# Hockii-Control.net
KiCad netlist of a schematic drawn in EAGLE
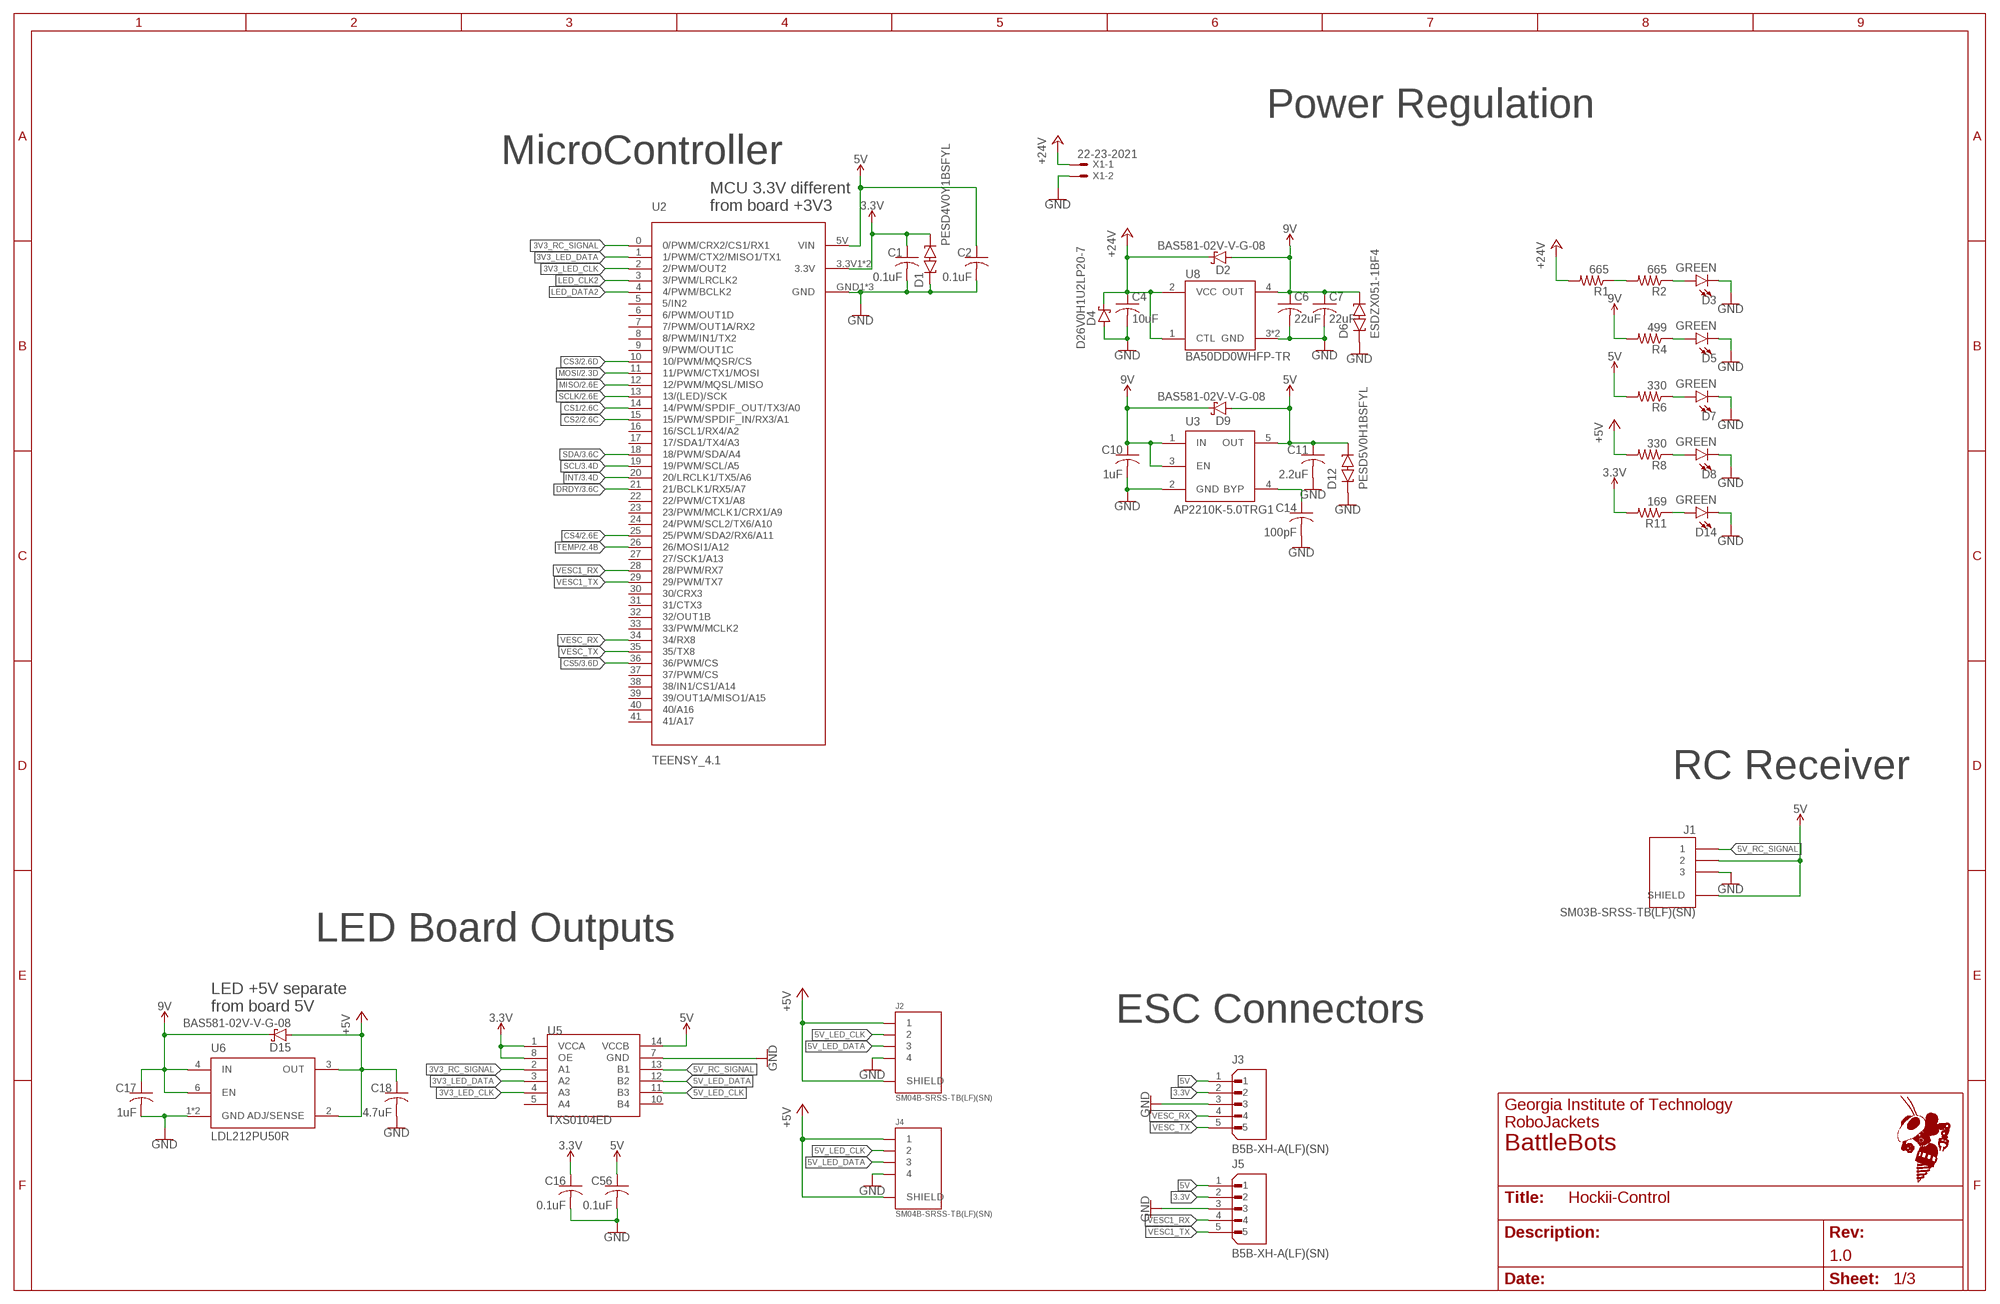
[diagram p0: schematic, sheet 1]
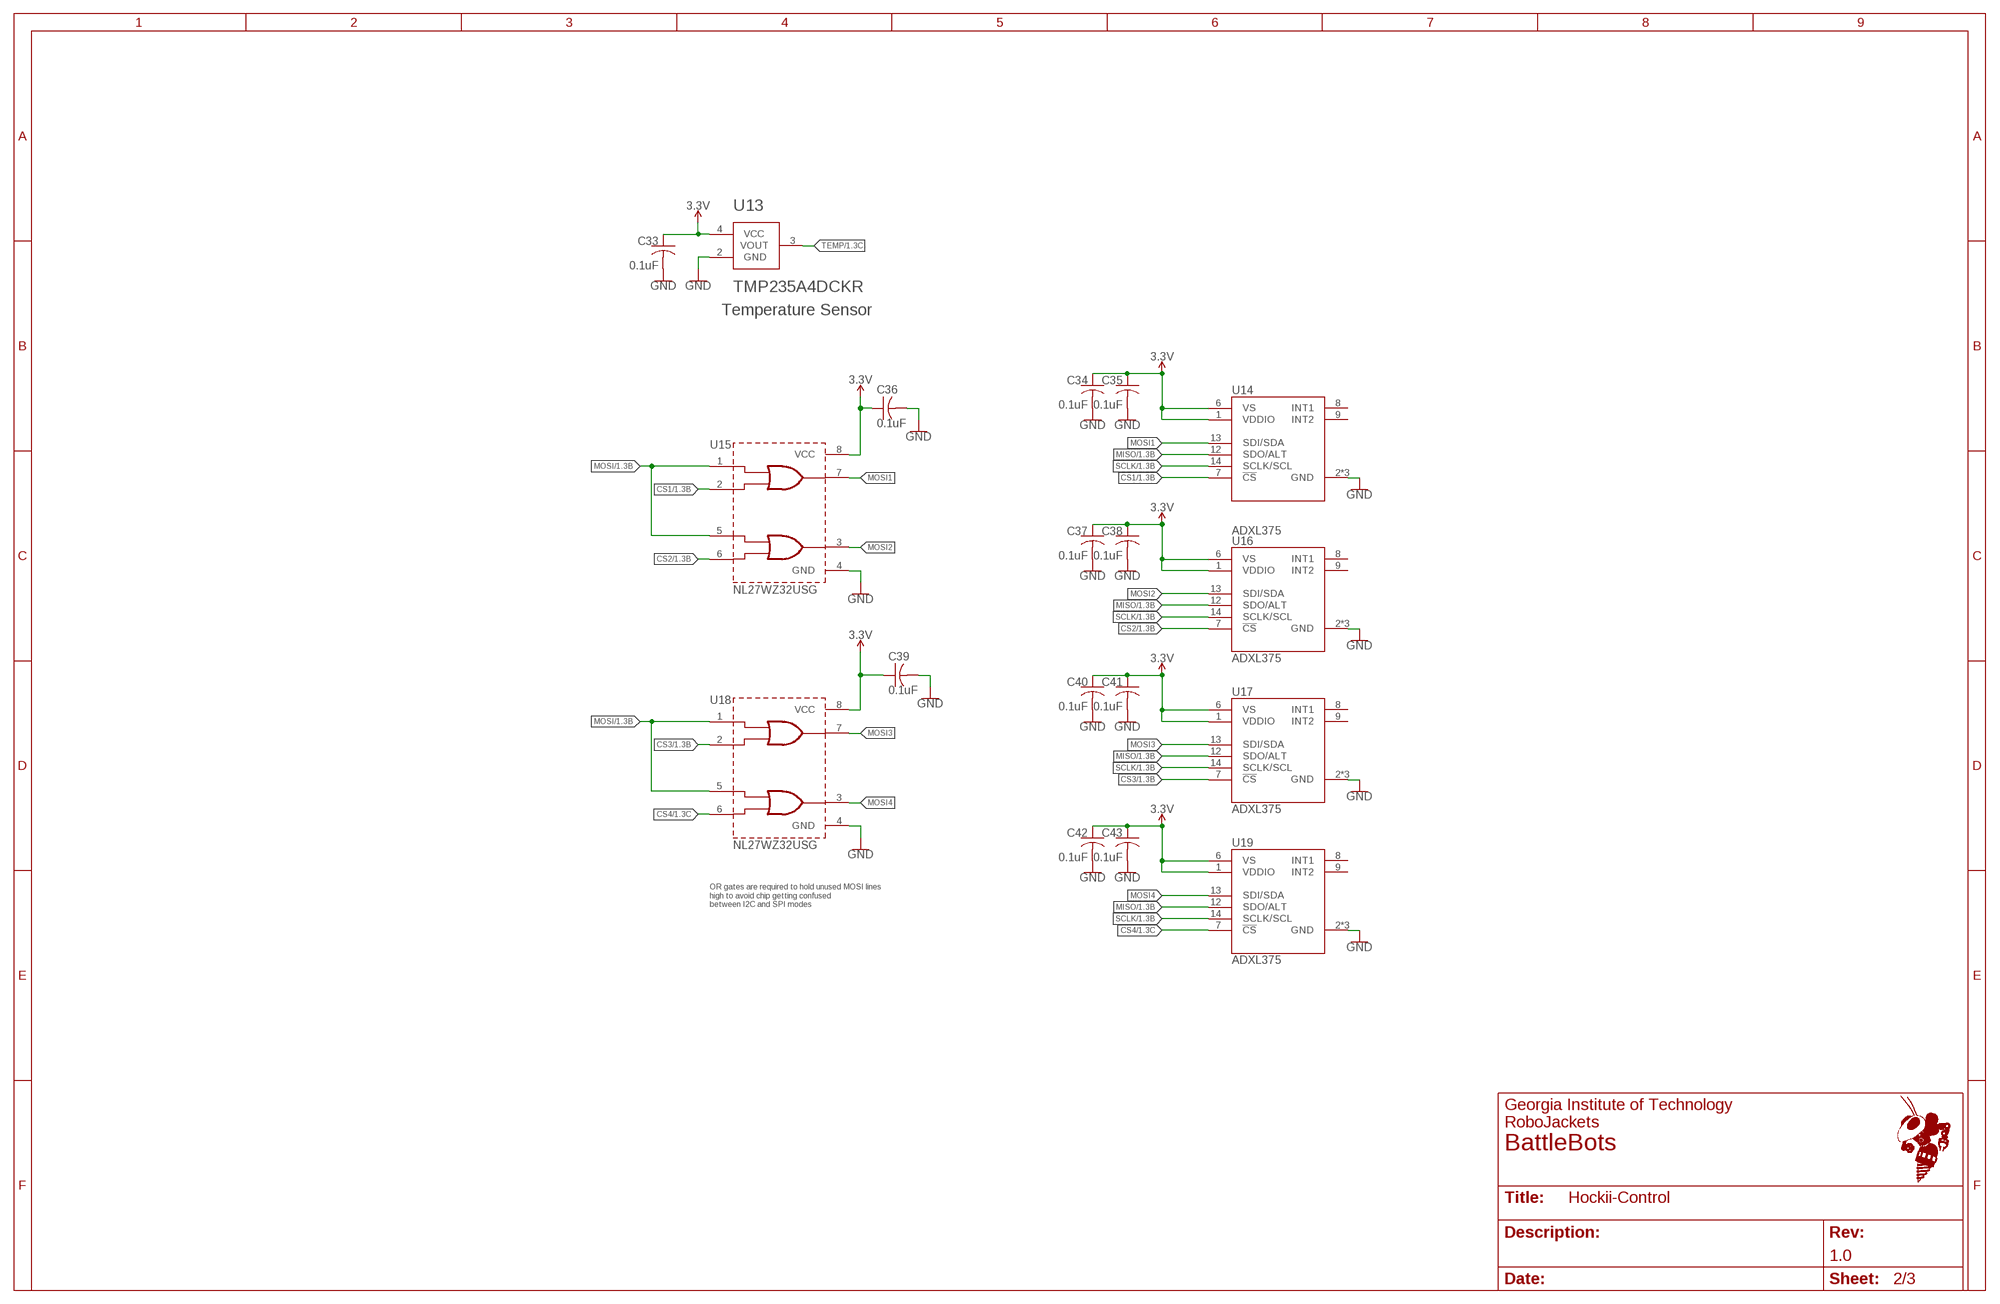
[diagram p1: schematic, sheet 2]
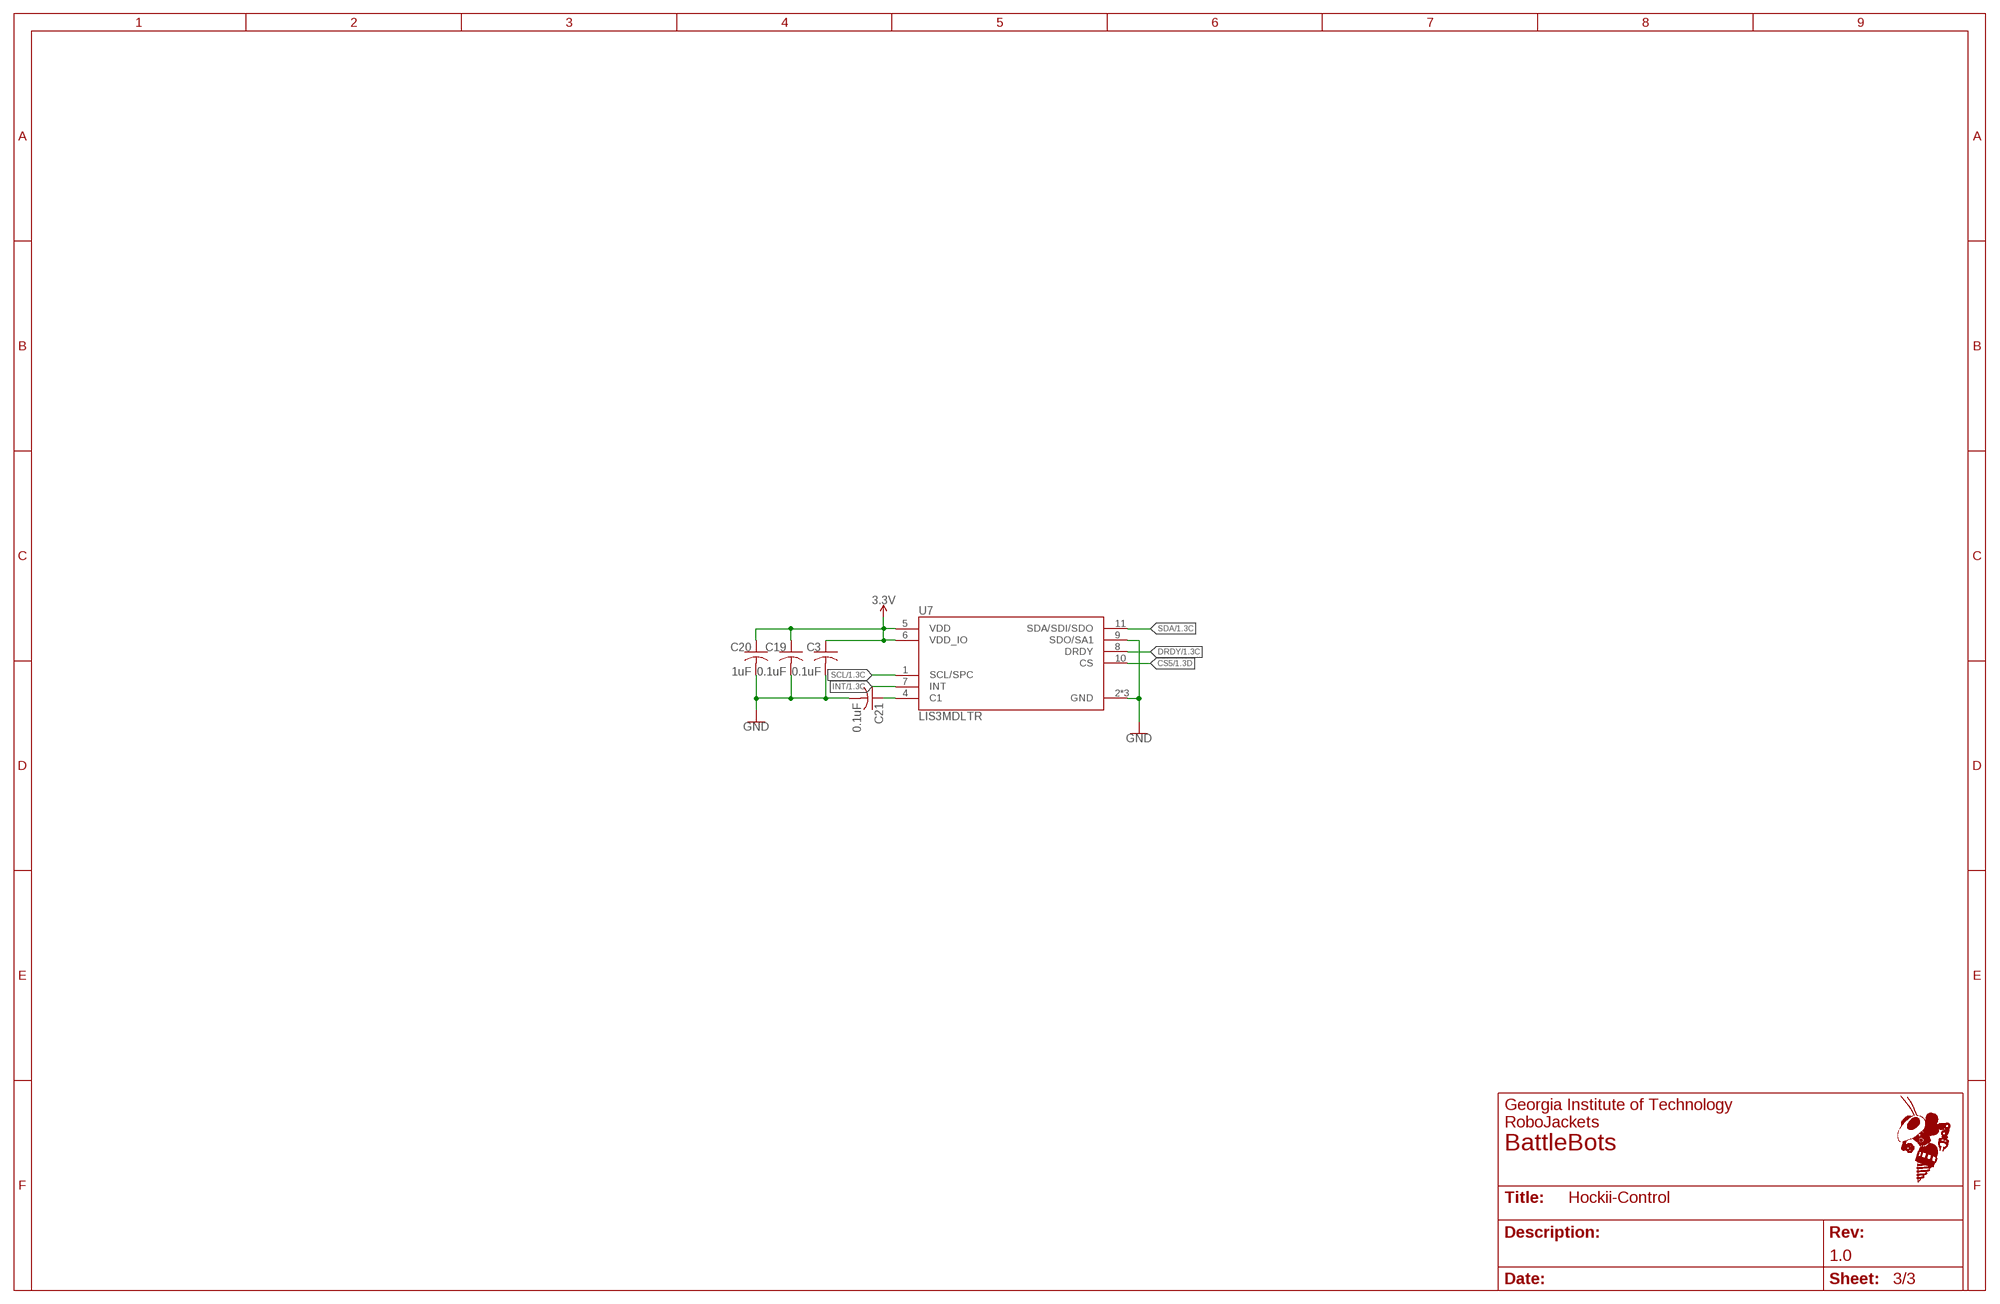
[diagram p2: schematic, sheet 3]

(export (version "E")
  (design (tool "Eeschema 10.0.6"))
  (components
    (comp (ref "C33")
      (value "0.1uF")
      (footprint "eagle-import:C0603")
      (libsource (lib "eagle-import") (part "C-USC0603"))
    )
    (comp (ref "C34")
      (value "0.1uF")
      (footprint "eagle-import:C0603")
      (libsource (lib "eagle-import") (part "C-USC0603"))
    )
    (comp (ref "C35")
      (value "0.1uF")
      (footprint "eagle-import:C0603")
      (libsource (lib "eagle-import") (part "C-USC0603"))
    )
    (comp (ref "C36")
      (value "0.1uF")
      (footprint "eagle-import:C0603")
      (libsource (lib "eagle-import") (part "C-USC0603"))
    )
    (comp (ref "C37")
      (value "0.1uF")
      (footprint "eagle-import:C0603")
      (libsource (lib "eagle-import") (part "C-USC0603"))
    )
    (comp (ref "C38")
      (value "0.1uF")
      (footprint "eagle-import:C0603")
      (libsource (lib "eagle-import") (part "C-USC0603"))
    )
    (comp (ref "C39")
      (value "0.1uF")
      (footprint "eagle-import:C0603")
      (libsource (lib "eagle-import") (part "C-USC0603"))
    )
    (comp (ref "C40")
      (value "0.1uF")
      (footprint "eagle-import:C0603")
      (libsource (lib "eagle-import") (part "C-USC0603"))
    )
    (comp (ref "C41")
      (value "0.1uF")
      (footprint "eagle-import:C0603")
      (libsource (lib "eagle-import") (part "C-USC0603"))
    )
    (comp (ref "C42")
      (value "0.1uF")
      (footprint "eagle-import:C0603")
      (libsource (lib "eagle-import") (part "C-USC0603"))
    )
    (comp (ref "C43")
      (value "0.1uF")
      (footprint "eagle-import:C0603")
      (libsource (lib "eagle-import") (part "C-USC0603"))
    )
    (comp (ref "U13")
      (value "TMP235A4DCKR")
      (footprint "eagle-import:SOT-353")
      (libsource (lib "eagle-import") (part "TMP235A4DCKR"))
    )
    (comp (ref "U14")
      (value "ADXL375")
      (footprint "eagle-import:14-LGA")
      (libsource (lib "eagle-import") (part "ADXL375"))
    )
    (comp (ref "U15")
      (value "NL27WZ32USG")
      (footprint "eagle-import:US8")
      (libsource (lib "eagle-import") (part "NL27WZ32USG"))
    )
    (comp (ref "U16")
      (value "ADXL375")
      (footprint "eagle-import:14-LGA")
      (libsource (lib "eagle-import") (part "ADXL375"))
    )
    (comp (ref "U17")
      (value "ADXL375")
      (footprint "eagle-import:14-LGA")
      (libsource (lib "eagle-import") (part "ADXL375"))
    )
    (comp (ref "U18")
      (value "NL27WZ32USG")
      (footprint "eagle-import:US8")
      (libsource (lib "eagle-import") (part "NL27WZ32USG"))
    )
    (comp (ref "U19")
      (value "ADXL375")
      (footprint "eagle-import:14-LGA")
      (libsource (lib "eagle-import") (part "ADXL375"))
    )
    (comp (ref "C3")
      (value "0.1uF")
      (footprint "eagle-import:C0603")
      (libsource (lib "eagle-import") (part "C-USC0603"))
    )
    (comp (ref "C19")
      (value "0.1uF")
      (footprint "eagle-import:C0603")
      (libsource (lib "eagle-import") (part "C-USC0603"))
    )
    (comp (ref "C20")
      (value "1uF")
      (footprint "eagle-import:C0603")
      (libsource (lib "eagle-import") (part "C-USC0603"))
    )
    (comp (ref "C21")
      (value "0.1uF")
      (footprint "eagle-import:C0603")
      (libsource (lib "eagle-import") (part "C-USC0603"))
    )
    (comp (ref "U7")
      (value "LIS3MDLTR")
      (footprint "eagle-import:LGA-12_2X2X1_STM")
      (libsource (lib "eagle-import") (part "LIS3MDLTR"))
    )
    (comp (ref "C1")
      (value "0.1uF")
      (footprint "eagle-import:C0603")
      (libsource (lib "eagle-import") (part "C-USC0603"))
    )
    (comp (ref "C2")
      (value "0.1uF")
      (footprint "eagle-import:C0603")
      (libsource (lib "eagle-import") (part "C-USC0603"))
    )
    (comp (ref "C4")
      (value "10uF")
      (footprint "eagle-import:C1206")
      (libsource (lib "eagle-import") (part "C-USC1206"))
    )
    (comp (ref "C6")
      (value "22uF")
      (footprint "eagle-import:C1206")
      (libsource (lib "eagle-import") (part "C-USC1206"))
    )
    (comp (ref "C7")
      (value "22uF")
      (footprint "eagle-import:C1206")
      (libsource (lib "eagle-import") (part "C-USC1206"))
    )
    (comp (ref "C10")
      (value "1uF")
      (footprint "eagle-import:C0603")
      (libsource (lib "eagle-import") (part "C-USC0603"))
    )
    (comp (ref "C11")
      (value "2.2uF")
      (footprint "eagle-import:C0603")
      (libsource (lib "eagle-import") (part "C-USC0603"))
    )
    (comp (ref "C14")
      (value "100pF")
      (footprint "eagle-import:C0603")
      (libsource (lib "eagle-import") (part "C-USC0603"))
    )
    (comp (ref "C16")
      (value "0.1uF")
      (footprint "eagle-import:C0603")
      (libsource (lib "eagle-import") (part "C-USC0603"))
    )
    (comp (ref "C17")
      (value "1uF")
      (footprint "eagle-import:C0603")
      (libsource (lib "eagle-import") (part "C-USC0603"))
    )
    (comp (ref "C18")
      (value "4.7uF")
      (footprint "eagle-import:C0603")
      (libsource (lib "eagle-import") (part "C-USC0603"))
    )
    (comp (ref "C56")
      (value "0.1uF")
      (footprint "eagle-import:C0603")
      (libsource (lib "eagle-import") (part "C-USC0603"))
    )
    (comp (ref "D1")
      (value "PESD4V0Y1BSFYL")
      (footprint "eagle-import:DSN0603-2")
      (libsource (lib "eagle-import") (part "PESD4V0Y1BSFYL"))
    )
    (comp (ref "D2")
      (value "BAS581-02V-V-G-08")
      (footprint "eagle-import:SOD-523")
      (libsource (lib "eagle-import") (part "BAS581-02V-V-G-08"))
    )
    (comp (ref "D3")
      (value "GREEN")
      (footprint "eagle-import:LED-0603")
      (libsource (lib "eagle-import") (part "LED-GREEN0603"))
    )
    (comp (ref "D4")
      (value "D26V0H1U2LP20-7")
      (footprint "eagle-import:D26V0H1U2LP20-7")
      (libsource (lib "eagle-import") (part "D26V0H1U2LP20-7"))
    )
    (comp (ref "D5")
      (value "GREEN")
      (footprint "eagle-import:LED-0603")
      (libsource (lib "eagle-import") (part "LED-GREEN0603"))
    )
    (comp (ref "D6")
      (value "ESDZX051-1BF4")
      (footprint "eagle-import:DSN0603-2")
      (libsource (lib "eagle-import") (part "ESDZX051-1BF4"))
    )
    (comp (ref "D7")
      (value "GREEN")
      (footprint "eagle-import:LED-0603")
      (libsource (lib "eagle-import") (part "LED-GREEN0603"))
    )
    (comp (ref "D8")
      (value "GREEN")
      (footprint "eagle-import:LED-0603")
      (libsource (lib "eagle-import") (part "LED-GREEN0603"))
    )
    (comp (ref "D9")
      (value "BAS581-02V-V-G-08")
      (footprint "eagle-import:SOD-523")
      (libsource (lib "eagle-import") (part "BAS581-02V-V-G-08"))
    )
    (comp (ref "D12")
      (value "PESD5V0H1BSFYL")
      (footprint "eagle-import:DSN0603-2")
      (libsource (lib "eagle-import") (part "PESD5V0H1BSFYL"))
    )
    (comp (ref "D14")
      (value "GREEN")
      (footprint "eagle-import:LED-0603")
      (libsource (lib "eagle-import") (part "LED-GREEN0603"))
    )
    (comp (ref "D15")
      (value "BAS581-02V-V-G-08")
      (footprint "eagle-import:SOD-523")
      (libsource (lib "eagle-import") (part "BAS581-02V-V-G-08"))
    )
    (comp (ref "J1")
      (value "SM03B-SRSS-TB(LF)(SN)")
      (footprint "eagle-import:SM03B-SRSS-TB(LF)(SN)")
      (libsource (lib "eagle-import") (part "SM03B-SRSS-TB(LF)(SN)"))
    )
    (comp (ref "J2")
      (value "SM04B-SRSS-TB(LF)(SN)")
      (footprint "eagle-import:SM04B-SRSS-TB(LF)(SN)")
      (libsource (lib "eagle-import") (part "SM04B-SRSS-TB(LF)(SN)"))
    )
    (comp (ref "J3")
      (value "B5B-XH-A(LF)(SN)")
      (footprint "eagle-import:JST_B5B-XH-A(LF)(SN)")
      (fields (field (name "MF") "JST Sales America Inc."))
      (libsource (lib "eagle-import") (part "B5B-XH-A(LF)(SN)"))
    )
    (comp (ref "J4")
      (value "SM04B-SRSS-TB(LF)(SN)")
      (footprint "eagle-import:SM04B-SRSS-TB(LF)(SN)")
      (libsource (lib "eagle-import") (part "SM04B-SRSS-TB(LF)(SN)"))
    )
    (comp (ref "J5")
      (value "B5B-XH-A(LF)(SN)")
      (footprint "eagle-import:JST_B5B-XH-A(LF)(SN)")
      (fields (field (name "MF") "JST Sales America Inc."))
      (libsource (lib "eagle-import") (part "B5B-XH-A(LF)(SN)"))
    )
    (comp (ref "R1")
      (value "665")
      (footprint "eagle-import:R0603")
      (libsource (lib "eagle-import") (part "R-US_R0603"))
    )
    (comp (ref "R2")
      (value "665")
      (footprint "eagle-import:R0603")
      (libsource (lib "eagle-import") (part "R-US_R0603"))
    )
    (comp (ref "R4")
      (value "499")
      (footprint "eagle-import:R0603")
      (libsource (lib "eagle-import") (part "R-US_R0603"))
    )
    (comp (ref "R6")
      (value "330")
      (footprint "eagle-import:R0603")
      (libsource (lib "eagle-import") (part "R-US_R0603"))
    )
    (comp (ref "R8")
      (value "330")
      (footprint "eagle-import:R0603")
      (libsource (lib "eagle-import") (part "R-US_R0603"))
    )
    (comp (ref "R11")
      (value "169")
      (footprint "eagle-import:R0603")
      (libsource (lib "eagle-import") (part "R-US_R0603"))
    )
    (comp (ref "U2")
      (value "TEENSY_4.1")
      (footprint "eagle-import:TEENSY_4.1")
      (libsource (lib "eagle-import") (part "TEENSY_4.1"))
    )
    (comp (ref "U3")
      (value "AP2210K-5.0TRG1")
      (footprint "eagle-import:SOT-23-5")
      (libsource (lib "eagle-import") (part "AP2210K-TRG15.0"))
    )
    (comp (ref "U5")
      (value "TXS0104ED")
      (footprint "eagle-import:14-SOIC")
      (libsource (lib "eagle-import") (part "TXS0104ED"))
    )
    (comp (ref "U6")
      (value "LDL212PU50R")
      (footprint "eagle-import:DFN6(3X3)")
      (libsource (lib "eagle-import") (part "LDL212PU50R"))
    )
    (comp (ref "U8")
      (value "BA50DD0WHFP-TR")
      (footprint "eagle-import:HRP5")
      (libsource (lib "eagle-import") (part "BA50DD0WHFP-TR"))
    )
    (comp (ref "X1")
      (value "22-23-2021")
      (footprint "eagle-import:22-23-2021")
      (fields (field (name "MF") "MOLEX"))
      (libsource (lib "eagle-import") (part "22-23-2021"))
    )
  )
  (nets
    (net (code "1") (name "+5V") (class "Default")
      (node (ref "C18") (pin "1") (pinfunction "1_1") (pintype "passive"))
      (node (ref "D15") (pin "2") (pinfunction "A_2") (pintype "passive"))
      (node (ref "J2") (pin "1") (pinfunction "1_1") (pintype "passive"))
      (node (ref "J2") (pin "S1") (pinfunction "SHIELD_S1") (pintype "passive"))
      (node (ref "J2") (pin "S2") (pinfunction "SHIELD_S2") (pintype "passive"))
      (node (ref "J4") (pin "1") (pinfunction "1_1") (pintype "passive"))
      (node (ref "J4") (pin "S1") (pinfunction "SHIELD_S1") (pintype "passive"))
      (node (ref "J4") (pin "S2") (pinfunction "SHIELD_S2") (pintype "passive"))
      (node (ref "R8") (pin "2") (pinfunction "2_2") (pintype "passive"))
      (node (ref "U6") (pin "2") (pinfunction "ADJ/SENSE_2") (pintype "bidirectional"))
      (node (ref "U6") (pin "3") (pinfunction "OUT_3") (pintype "passive"))
    )
    (net (code "2") (name "+24V") (class "Default")
      (node (ref "C4") (pin "1") (pinfunction "1_1") (pintype "passive"))
      (node (ref "D2") (pin "1") (pinfunction "C_1") (pintype "passive"))
      (node (ref "D4") (pin "1") (pinfunction "C_1") (pintype "passive"))
      (node (ref "R1") (pin "2") (pinfunction "2_2") (pintype "passive"))
      (node (ref "U8") (pin "1") (pinfunction "CTL_1") (pintype "input"))
      (node (ref "U8") (pin "2") (pinfunction "VCC_2") (pintype "power_in"))
      (node (ref "X1") (pin "1") (pinfunction "S_1") (pintype "passive"))
    )
    (net (code "3") (name "3.3V") (class "Default")
      (node (ref "C1") (pin "1") (pinfunction "1_1") (pintype "passive"))
      (node (ref "C16") (pin "1") (pinfunction "1_1") (pintype "passive"))
      (node (ref "C19") (pin "1") (pinfunction "1_1") (pintype "passive"))
      (node (ref "C20") (pin "1") (pinfunction "1_1") (pintype "passive"))
      (node (ref "C3") (pin "1") (pinfunction "1_1") (pintype "passive"))
      (node (ref "C33") (pin "1") (pinfunction "1_1") (pintype "passive"))
      (node (ref "C34") (pin "1") (pinfunction "1_1") (pintype "passive"))
      (node (ref "C35") (pin "1") (pinfunction "1_1") (pintype "passive"))
      (node (ref "C36") (pin "1") (pinfunction "1_1") (pintype "passive"))
      (node (ref "C37") (pin "1") (pinfunction "1_1") (pintype "passive"))
      (node (ref "C38") (pin "1") (pinfunction "1_1") (pintype "passive"))
      (node (ref "C39") (pin "1") (pinfunction "1_1") (pintype "passive"))
      (node (ref "C40") (pin "1") (pinfunction "1_1") (pintype "passive"))
      (node (ref "C41") (pin "1") (pinfunction "1_1") (pintype "passive"))
      (node (ref "C42") (pin "1") (pinfunction "1_1") (pintype "passive"))
      (node (ref "C43") (pin "1") (pinfunction "1_1") (pintype "passive"))
      (node (ref "D1") (pin "C2") (pinfunction "C2_C2") (pintype "passive"))
      (node (ref "J3") (pin "2") (pinfunction "2_2") (pintype "passive"))
      (node (ref "J5") (pin "2") (pinfunction "2_2") (pintype "passive"))
      (node (ref "R11") (pin "2") (pinfunction "2_2") (pintype "passive"))
      (node (ref "U13") (pin "4") (pinfunction "VCC_4") (pintype "passive"))
      (node (ref "U14") (pin "1") (pinfunction "VDDIO_1") (pintype "passive"))
      (node (ref "U14") (pin "6") (pinfunction "VS_6") (pintype "passive"))
      (node (ref "U15") (pin "8") (pinfunction "VCC_8") (pintype "passive"))
      (node (ref "U16") (pin "1") (pinfunction "VDDIO_1") (pintype "passive"))
      (node (ref "U16") (pin "6") (pinfunction "VS_6") (pintype "passive"))
      (node (ref "U17") (pin "1") (pinfunction "VDDIO_1") (pintype "passive"))
      (node (ref "U17") (pin "6") (pinfunction "VS_6") (pintype "passive"))
      (node (ref "U18") (pin "8") (pinfunction "VCC_8") (pintype "passive"))
      (node (ref "U19") (pin "1") (pinfunction "VDDIO_1") (pintype "passive"))
      (node (ref "U19") (pin "6") (pinfunction "VS_6") (pintype "passive"))
      (node (ref "U2") (pin "3.3V1") (pinfunction "3.3V_3.3V1") (pintype "passive"))
      (node (ref "U2") (pin "3.3V2") (pinfunction "3.3V_3.3V2") (pintype "passive"))
      (node (ref "U5") (pin "1") (pinfunction "VCCA_1") (pintype "passive"))
      (node (ref "U5") (pin "8") (pinfunction "OE_8") (pintype "passive"))
      (node (ref "U7") (pin "5") (pinfunction "VDD_5") (pintype "passive"))
      (node (ref "U7") (pin "6") (pinfunction "VDD_IO_6") (pintype "passive"))
    )
    (net (code "4") (name "3V3_LED_CLK") (class "Default")
      (node (ref "U2") (pin "2") (pinfunction "2/PWM/OUT2_2") (pintype "passive"))
      (node (ref "U5") (pin "4") (pinfunction "A3_4") (pintype "passive"))
    )
    (net (code "5") (name "3V3_LED_DATA") (class "Default")
      (node (ref "U2") (pin "1") (pinfunction "1/PWM/CTX2/MISO1/TX1_1") (pintype "passive"))
      (node (ref "U5") (pin "3") (pinfunction "A2_3") (pintype "passive"))
    )
    (net (code "6") (name "3V3_RC_SIGNAL") (class "Default")
      (node (ref "U2") (pin "0") (pinfunction "0/PWM/CRX2/CS1/RX1_0") (pintype "passive"))
      (node (ref "U5") (pin "2") (pinfunction "A1_2") (pintype "passive"))
    )
    (net (code "7") (name "5V") (class "Default")
      (node (ref "C11") (pin "1") (pinfunction "1_1") (pintype "passive"))
      (node (ref "C2") (pin "1") (pinfunction "1_1") (pintype "passive"))
      (node (ref "C56") (pin "1") (pinfunction "1_1") (pintype "passive"))
      (node (ref "D12") (pin "C2") (pinfunction "C2_C2") (pintype "passive"))
      (node (ref "D9") (pin "2") (pinfunction "A_2") (pintype "passive"))
      (node (ref "J1") (pin "2") (pinfunction "2_2") (pintype "passive"))
      (node (ref "J1") (pin "S1") (pinfunction "SHIELD_S1") (pintype "passive"))
      (node (ref "J1") (pin "S2") (pinfunction "SHIELD_S2") (pintype "passive"))
      (node (ref "J3") (pin "1") (pinfunction "1_1") (pintype "passive"))
      (node (ref "J5") (pin "1") (pinfunction "1_1") (pintype "passive"))
      (node (ref "R6") (pin "2") (pinfunction "2_2") (pintype "passive"))
      (node (ref "U2") (pin "5V") (pinfunction "VIN_5V") (pintype "passive"))
      (node (ref "U3") (pin "5") (pinfunction "OUT_5") (pintype "passive"))
      (node (ref "U5") (pin "14") (pinfunction "VCCB_14") (pintype "passive"))
    )
    (net (code "8") (name "5V_LED_CLK") (class "Default")
      (node (ref "J2") (pin "2") (pinfunction "2_2") (pintype "passive"))
      (node (ref "J4") (pin "2") (pinfunction "2_2") (pintype "passive"))
      (node (ref "U5") (pin "11") (pinfunction "B3_11") (pintype "passive"))
    )
    (net (code "9") (name "5V_LED_DATA") (class "Default")
      (node (ref "J2") (pin "3") (pinfunction "3_3") (pintype "passive"))
      (node (ref "J4") (pin "3") (pinfunction "3_3") (pintype "passive"))
      (node (ref "U5") (pin "12") (pinfunction "B2_12") (pintype "passive"))
    )
    (net (code "10") (name "5V_RC_SIGNAL") (class "Default")
      (node (ref "J1") (pin "1") (pinfunction "1_1") (pintype "passive"))
      (node (ref "U5") (pin "13") (pinfunction "B1_13") (pintype "passive"))
    )
    (net (code "11") (name "9V") (class "Default")
      (node (ref "C10") (pin "1") (pinfunction "1_1") (pintype "passive"))
      (node (ref "C17") (pin "1") (pinfunction "1_1") (pintype "passive"))
      (node (ref "C6") (pin "1") (pinfunction "1_1") (pintype "passive"))
      (node (ref "C7") (pin "1") (pinfunction "1_1") (pintype "passive"))
      (node (ref "D15") (pin "1") (pinfunction "C_1") (pintype "passive"))
      (node (ref "D2") (pin "2") (pinfunction "A_2") (pintype "passive"))
      (node (ref "D6") (pin "C2") (pinfunction "C2_C2") (pintype "passive"))
      (node (ref "D9") (pin "1") (pinfunction "C_1") (pintype "passive"))
      (node (ref "R4") (pin "2") (pinfunction "2_2") (pintype "passive"))
      (node (ref "U3") (pin "1") (pinfunction "IN_1") (pintype "passive"))
      (node (ref "U3") (pin "3") (pinfunction "EN_3") (pintype "passive"))
      (node (ref "U6") (pin "4") (pinfunction "IN_4") (pintype "passive"))
      (node (ref "U6") (pin "6") (pinfunction "EN_6") (pintype "passive"))
      (node (ref "U8") (pin "4") (pinfunction "OUT_4") (pintype "output"))
    )
    (net (code "12") (name "CS1") (class "Default")
      (node (ref "U14") (pin "7") (pinfunction "~{CS}_7") (pintype "passive"))
      (node (ref "U15") (pin "2") (pinfunction "B1_2") (pintype "passive"))
      (node (ref "U2") (pin "14") (pinfunction "14/PWM/SPDIF_OUT/TX3/A0_14") (pintype "passive"))
    )
    (net (code "13") (name "CS2") (class "Default")
      (node (ref "U15") (pin "6") (pinfunction "B2_6") (pintype "passive"))
      (node (ref "U16") (pin "7") (pinfunction "~{CS}_7") (pintype "passive"))
      (node (ref "U2") (pin "15") (pinfunction "15/PWM/SPDIF_IN/RX3/A1_15") (pintype "passive"))
    )
    (net (code "14") (name "CS3") (class "Default")
      (node (ref "U17") (pin "7") (pinfunction "~{CS}_7") (pintype "passive"))
      (node (ref "U18") (pin "2") (pinfunction "B1_2") (pintype "passive"))
      (node (ref "U2") (pin "10") (pinfunction "10/PWM/MQSR/CS_10") (pintype "passive"))
    )
    (net (code "15") (name "CS4") (class "Default")
      (node (ref "U18") (pin "6") (pinfunction "B2_6") (pintype "passive"))
      (node (ref "U19") (pin "7") (pinfunction "~{CS}_7") (pintype "passive"))
      (node (ref "U2") (pin "25") (pinfunction "25/PWM/SDA2/RX6/A11_25") (pintype "passive"))
    )
    (net (code "16") (name "CS5") (class "Default")
      (node (ref "U2") (pin "36") (pinfunction "36/PWM/CS_36") (pintype "passive"))
      (node (ref "U7") (pin "10") (pinfunction "CS_10") (pintype "passive"))
    )
    (net (code "17") (name "DRDY") (class "Default")
      (node (ref "U2") (pin "21") (pinfunction "21/BCLK1/RX5/A7_21") (pintype "passive"))
      (node (ref "U7") (pin "8") (pinfunction "DRDY_8") (pintype "passive"))
    )
    (net (code "18") (name "GND") (class "Default")
      (node (ref "C1") (pin "2") (pinfunction "2_2") (pintype "passive"))
      (node (ref "C10") (pin "2") (pinfunction "2_2") (pintype "passive"))
      (node (ref "C11") (pin "2") (pinfunction "2_2") (pintype "passive"))
      (node (ref "C14") (pin "2") (pinfunction "2_2") (pintype "passive"))
      (node (ref "C16") (pin "2") (pinfunction "2_2") (pintype "passive"))
      (node (ref "C17") (pin "2") (pinfunction "2_2") (pintype "passive"))
      (node (ref "C18") (pin "2") (pinfunction "2_2") (pintype "passive"))
      (node (ref "C19") (pin "2") (pinfunction "2_2") (pintype "passive"))
      (node (ref "C2") (pin "2") (pinfunction "2_2") (pintype "passive"))
      (node (ref "C20") (pin "2") (pinfunction "2_2") (pintype "passive"))
      (node (ref "C21") (pin "2") (pinfunction "2_2") (pintype "passive"))
      (node (ref "C3") (pin "2") (pinfunction "2_2") (pintype "passive"))
      (node (ref "C33") (pin "2") (pinfunction "2_2") (pintype "passive"))
      (node (ref "C34") (pin "2") (pinfunction "2_2") (pintype "passive"))
      (node (ref "C35") (pin "2") (pinfunction "2_2") (pintype "passive"))
      (node (ref "C36") (pin "2") (pinfunction "2_2") (pintype "passive"))
      (node (ref "C37") (pin "2") (pinfunction "2_2") (pintype "passive"))
      (node (ref "C38") (pin "2") (pinfunction "2_2") (pintype "passive"))
      (node (ref "C39") (pin "2") (pinfunction "2_2") (pintype "passive"))
      (node (ref "C4") (pin "2") (pinfunction "2_2") (pintype "passive"))
      (node (ref "C40") (pin "2") (pinfunction "2_2") (pintype "passive"))
      (node (ref "C41") (pin "2") (pinfunction "2_2") (pintype "passive"))
      (node (ref "C42") (pin "2") (pinfunction "2_2") (pintype "passive"))
      (node (ref "C43") (pin "2") (pinfunction "2_2") (pintype "passive"))
      (node (ref "C56") (pin "2") (pinfunction "2_2") (pintype "passive"))
      (node (ref "C6") (pin "2") (pinfunction "2_2") (pintype "passive"))
      (node (ref "C7") (pin "2") (pinfunction "2_2") (pintype "passive"))
      (node (ref "D1") (pin "C1") (pinfunction "C1_C1") (pintype "passive"))
      (node (ref "D12") (pin "C1") (pinfunction "C1_C1") (pintype "passive"))
      (node (ref "D14") (pin "C") (pinfunction "C_C") (pintype "passive"))
      (node (ref "D3") (pin "C") (pinfunction "C_C") (pintype "passive"))
      (node (ref "D4") (pin "2") (pinfunction "A_2") (pintype "passive"))
      (node (ref "D5") (pin "C") (pinfunction "C_C") (pintype "passive"))
      (node (ref "D6") (pin "C1") (pinfunction "C1_C1") (pintype "passive"))
      (node (ref "D7") (pin "C") (pinfunction "C_C") (pintype "passive"))
      (node (ref "D8") (pin "C") (pinfunction "C_C") (pintype "passive"))
      (node (ref "J1") (pin "3") (pinfunction "3_3") (pintype "passive"))
      (node (ref "J2") (pin "4") (pinfunction "4_4") (pintype "passive"))
      (node (ref "J3") (pin "3") (pinfunction "3_3") (pintype "passive"))
      (node (ref "J4") (pin "4") (pinfunction "4_4") (pintype "passive"))
      (node (ref "J5") (pin "3") (pinfunction "3_3") (pintype "passive"))
      (node (ref "U13") (pin "2") (pinfunction "GND_2") (pintype "passive"))
      (node (ref "U14") (pin "2") (pinfunction "GND_2") (pintype "passive"))
      (node (ref "U14") (pin "4") (pinfunction "GND_4") (pintype "passive"))
      (node (ref "U14") (pin "5") (pinfunction "GND_5") (pintype "passive"))
      (node (ref "U15") (pin "4") (pinfunction "GND_4") (pintype "passive"))
      (node (ref "U16") (pin "2") (pinfunction "GND_2") (pintype "passive"))
      (node (ref "U16") (pin "4") (pinfunction "GND_4") (pintype "passive"))
      (node (ref "U16") (pin "5") (pinfunction "GND_5") (pintype "passive"))
      (node (ref "U17") (pin "2") (pinfunction "GND_2") (pintype "passive"))
      (node (ref "U17") (pin "4") (pinfunction "GND_4") (pintype "passive"))
      (node (ref "U17") (pin "5") (pinfunction "GND_5") (pintype "passive"))
      (node (ref "U18") (pin "4") (pinfunction "GND_4") (pintype "passive"))
      (node (ref "U19") (pin "2") (pinfunction "GND_2") (pintype "passive"))
      (node (ref "U19") (pin "4") (pinfunction "GND_4") (pintype "passive"))
      (node (ref "U19") (pin "5") (pinfunction "GND_5") (pintype "passive"))
      (node (ref "U2") (pin "GND1") (pinfunction "GND_GND1") (pintype "passive"))
      (node (ref "U2") (pin "GND2") (pinfunction "GND_GND2") (pintype "passive"))
      (node (ref "U2") (pin "GND3") (pinfunction "GND_GND3") (pintype "passive"))
      (node (ref "U3") (pin "2") (pinfunction "GND_2") (pintype "passive"))
      (node (ref "U5") (pin "7") (pinfunction "GND_7") (pintype "passive"))
      (node (ref "U6") (pin "1") (pinfunction "GND_1") (pintype "passive"))
      (node (ref "U6") (pin "7") (pinfunction "GND_7") (pintype "passive"))
      (node (ref "U7") (pin "12") (pinfunction "GND_12") (pintype "passive"))
      (node (ref "U7") (pin "2") (pinfunction "GND_2") (pintype "passive"))
      (node (ref "U7") (pin "3") (pinfunction "GND_3") (pintype "passive"))
      (node (ref "U7") (pin "9") (pinfunction "SDO/SA1_9") (pintype "passive"))
      (node (ref "U8") (pin "3") (pinfunction "GND_3") (pintype "power_in"))
      (node (ref "U8") (pin "6") (pinfunction "GND_6") (pintype "power_in"))
      (node (ref "X1") (pin "2") (pinfunction "S_2") (pintype "passive"))
    )
    (net (code "19") (name "INT") (class "Default")
      (node (ref "U2") (pin "20") (pinfunction "20/LRCLK1/TX5/A6_20") (pintype "passive"))
      (node (ref "U7") (pin "7") (pinfunction "INT_7") (pintype "passive"))
    )
    (net (code "20") (name "LED_CLK2") (class "Default")
      (node (ref "U2") (pin "3") (pinfunction "3/PWM/LRCLK2_3") (pintype "passive"))
    )
    (net (code "21") (name "LED_DATA2") (class "Default")
      (node (ref "U2") (pin "4") (pinfunction "4/PWM/BCLK2_4") (pintype "passive"))
    )
    (net (code "22") (name "MISO") (class "Default")
      (node (ref "U14") (pin "12") (pinfunction "SDO/ALT_12") (pintype "passive"))
      (node (ref "U16") (pin "12") (pinfunction "SDO/ALT_12") (pintype "passive"))
      (node (ref "U17") (pin "12") (pinfunction "SDO/ALT_12") (pintype "passive"))
      (node (ref "U19") (pin "12") (pinfunction "SDO/ALT_12") (pintype "passive"))
      (node (ref "U2") (pin "12") (pinfunction "12/PWM/MQSL/MISO_12") (pintype "passive"))
    )
    (net (code "23") (name "MOSI") (class "Default")
      (node (ref "U15") (pin "1") (pinfunction "A1_1") (pintype "passive"))
      (node (ref "U15") (pin "5") (pinfunction "A2_5") (pintype "passive"))
      (node (ref "U18") (pin "1") (pinfunction "A1_1") (pintype "passive"))
      (node (ref "U18") (pin "5") (pinfunction "A2_5") (pintype "passive"))
      (node (ref "U2") (pin "11") (pinfunction "11/PWM/CTX1/MOSI_11") (pintype "passive"))
    )
    (net (code "24") (name "MOSI1") (class "Default")
      (node (ref "U14") (pin "13") (pinfunction "SDI/SDA_13") (pintype "passive"))
      (node (ref "U15") (pin "7") (pinfunction "Y1_7") (pintype "passive"))
    )
    (net (code "25") (name "MOSI2") (class "Default")
      (node (ref "U15") (pin "3") (pinfunction "Y2_3") (pintype "passive"))
      (node (ref "U16") (pin "13") (pinfunction "SDI/SDA_13") (pintype "passive"))
    )
    (net (code "26") (name "MOSI3") (class "Default")
      (node (ref "U17") (pin "13") (pinfunction "SDI/SDA_13") (pintype "passive"))
      (node (ref "U18") (pin "7") (pinfunction "Y1_7") (pintype "passive"))
    )
    (net (code "27") (name "MOSI4") (class "Default")
      (node (ref "U18") (pin "3") (pinfunction "Y2_3") (pintype "passive"))
      (node (ref "U19") (pin "13") (pinfunction "SDI/SDA_13") (pintype "passive"))
    )
    (net (code "28") (name "Net-(D3-PadA)") (class "Default")
      (node (ref "D3") (pin "A") (pinfunction "A_A") (pintype "passive"))
      (node (ref "R2") (pin "1") (pinfunction "1_1") (pintype "passive"))
    )
    (net (code "29") (name "Net-(D5-PadA)") (class "Default")
      (node (ref "D5") (pin "A") (pinfunction "A_A") (pintype "passive"))
      (node (ref "R4") (pin "1") (pinfunction "1_1") (pintype "passive"))
    )
    (net (code "30") (name "Net-(D7-PadA)") (class "Default")
      (node (ref "D7") (pin "A") (pinfunction "A_A") (pintype "passive"))
      (node (ref "R6") (pin "1") (pinfunction "1_1") (pintype "passive"))
    )
    (net (code "31") (name "Net-(D8-PadA)") (class "Default")
      (node (ref "D8") (pin "A") (pinfunction "A_A") (pintype "passive"))
      (node (ref "R8") (pin "1") (pinfunction "1_1") (pintype "passive"))
    )
    (net (code "32") (name "Net-(D14-PadA)") (class "Default")
      (node (ref "D14") (pin "A") (pinfunction "A_A") (pintype "passive"))
      (node (ref "R11") (pin "1") (pinfunction "1_1") (pintype "passive"))
    )
    (net (code "33") (name "Net-(R1-Pad1)") (class "Default")
      (node (ref "R1") (pin "1") (pinfunction "1_1") (pintype "passive"))
      (node (ref "R2") (pin "2") (pinfunction "2_2") (pintype "passive"))
    )
    (net (code "34") (name "Net-(U3-BYP)") (class "Default")
      (node (ref "C14") (pin "1") (pinfunction "1_1") (pintype "passive"))
      (node (ref "U3") (pin "4") (pinfunction "BYP_4") (pintype "bidirectional"))
    )
    (net (code "35") (name "Net-(U7-C1)") (class "Default")
      (node (ref "C21") (pin "1") (pinfunction "1_1") (pintype "passive"))
      (node (ref "U7") (pin "4") (pinfunction "C1_4") (pintype "passive"))
    )
    (net (code "36") (name "SCL") (class "Default")
      (node (ref "U2") (pin "19") (pinfunction "19/PWM/SCL/A5_19") (pintype "passive"))
      (node (ref "U7") (pin "1") (pinfunction "SCL/SPC_1") (pintype "passive"))
    )
    (net (code "37") (name "SCLK") (class "Default")
      (node (ref "U14") (pin "14") (pinfunction "SCLK/SCL_14") (pintype "passive"))
      (node (ref "U16") (pin "14") (pinfunction "SCLK/SCL_14") (pintype "passive"))
      (node (ref "U17") (pin "14") (pinfunction "SCLK/SCL_14") (pintype "passive"))
      (node (ref "U19") (pin "14") (pinfunction "SCLK/SCL_14") (pintype "passive"))
      (node (ref "U2") (pin "13") (pinfunction "13/(LED)/SCK_13") (pintype "passive"))
    )
    (net (code "38") (name "SDA") (class "Default")
      (node (ref "U2") (pin "18") (pinfunction "18/PWM/SDA/A4_18") (pintype "passive"))
      (node (ref "U7") (pin "11") (pinfunction "SDA/SDI/SDO_11") (pintype "passive"))
    )
    (net (code "39") (name "TEMP") (class "Default")
      (node (ref "U13") (pin "3") (pinfunction "VOUT_3") (pintype "passive"))
      (node (ref "U2") (pin "26") (pinfunction "26/MOSI1/A12_26") (pintype "passive"))
    )
    (net (code "40") (name "VESC1_RX") (class "Default")
      (node (ref "J5") (pin "4") (pinfunction "4_4") (pintype "passive"))
      (node (ref "U2") (pin "28") (pinfunction "28/PWM/RX7_28") (pintype "passive"))
    )
    (net (code "41") (name "VESC1_TX") (class "Default")
      (node (ref "J5") (pin "5") (pinfunction "5_5") (pintype "passive"))
      (node (ref "U2") (pin "29") (pinfunction "29/PWM/TX7_29") (pintype "passive"))
    )
    (net (code "42") (name "VESC_RX") (class "Default")
      (node (ref "J3") (pin "4") (pinfunction "4_4") (pintype "passive"))
      (node (ref "U2") (pin "34") (pinfunction "34/RX8_34") (pintype "passive"))
    )
    (net (code "43") (name "VESC_TX") (class "Default")
      (node (ref "J3") (pin "5") (pinfunction "5_5") (pintype "passive"))
      (node (ref "U2") (pin "35") (pinfunction "35/TX8_35") (pintype "passive"))
    )
    (net (code "44") (name "unconnected-(U2-5{slash}IN2-Pad5)") (class "Default")
      (node (ref "U2") (pin "5") (pinfunction "5/IN2_5") (pintype "passive"))
    )
    (net (code "45") (name "unconnected-(U2-6{slash}PWM{slash}OUT1D-Pad6)") (class "Default")
      (node (ref "U2") (pin "6") (pinfunction "6/PWM/OUT1D_6") (pintype "passive"))
    )
    (net (code "46") (name "unconnected-(U2-7{slash}PWM{slash}OUT1A{slash}RX2-Pad7)") (class "Default")
      (node (ref "U2") (pin "7") (pinfunction "7/PWM/OUT1A/RX2_7") (pintype "passive"))
    )
    (net (code "47") (name "unconnected-(U2-8{slash}PWM{slash}IN1{slash}TX2-Pad8)") (class "Default")
      (node (ref "U2") (pin "8") (pinfunction "8/PWM/IN1/TX2_8") (pintype "passive"))
    )
    (net (code "48") (name "unconnected-(U2-9{slash}PWM{slash}OUT1C-Pad9)") (class "Default")
      (node (ref "U2") (pin "9") (pinfunction "9/PWM/OUT1C_9") (pintype "passive"))
    )
    (net (code "49") (name "unconnected-(U2-16{slash}SCL1{slash}RX4{slash}A2-Pad16)") (class "Default")
      (node (ref "U2") (pin "16") (pinfunction "16/SCL1/RX4/A2_16") (pintype "passive"))
    )
    (net (code "50") (name "unconnected-(U2-17{slash}SDA1{slash}TX4{slash}A3-Pad17)") (class "Default")
      (node (ref "U2") (pin "17") (pinfunction "17/SDA1/TX4/A3_17") (pintype "passive"))
    )
    (net (code "51") (name "unconnected-(U2-22{slash}PWM{slash}CTX1{slash}A8-Pad22)") (class "Default")
      (node (ref "U2") (pin "22") (pinfunction "22/PWM/CTX1/A8_22") (pintype "passive"))
    )
    (net (code "52") (name "unconnected-(U2-23{slash}PWM{slash}MCLK1{slash}CRX1{slash}A9-Pad23)") (class "Default")
      (node (ref "U2") (pin "23") (pinfunction "23/PWM/MCLK1/CRX1/A9_23") (pintype "passive"))
    )
    (net (code "53") (name "unconnected-(U2-24{slash}PWM{slash}SCL2{slash}TX6{slash}A10-Pad24)") (class "Default")
      (node (ref "U2") (pin "24") (pinfunction "24/PWM/SCL2/TX6/A10_24") (pintype "passive"))
    )
    (net (code "54") (name "unconnected-(U2-27{slash}SCK1{slash}A13-Pad27)") (class "Default")
      (node (ref "U2") (pin "27") (pinfunction "27/SCK1/A13_27") (pintype "passive"))
    )
    (net (code "55") (name "unconnected-(U2-30{slash}CRX3-Pad30)") (class "Default")
      (node (ref "U2") (pin "30") (pinfunction "30/CRX3_30") (pintype "passive"))
    )
    (net (code "56") (name "unconnected-(U2-31{slash}CTX3-Pad31)") (class "Default")
      (node (ref "U2") (pin "31") (pinfunction "31/CTX3_31") (pintype "passive"))
    )
    (net (code "57") (name "unconnected-(U2-32{slash}OUT1B-Pad32)") (class "Default")
      (node (ref "U2") (pin "32") (pinfunction "32/OUT1B_32") (pintype "passive"))
    )
    (net (code "58") (name "unconnected-(U2-33{slash}PWM{slash}MCLK2-Pad33)") (class "Default")
      (node (ref "U2") (pin "33") (pinfunction "33/PWM/MCLK2_33") (pintype "passive"))
    )
    (net (code "59") (name "unconnected-(U2-37{slash}PWM{slash}CS-Pad37)") (class "Default")
      (node (ref "U2") (pin "37") (pinfunction "37/PWM/CS_37") (pintype "passive"))
    )
    (net (code "60") (name "unconnected-(U2-38{slash}IN1{slash}CS1{slash}A14-Pad38)") (class "Default")
      (node (ref "U2") (pin "38") (pinfunction "38/IN1/CS1/A14_38") (pintype "passive"))
    )
    (net (code "61") (name "unconnected-(U2-39{slash}OUT1A{slash}MISO1{slash}A15-Pad39)") (class "Default")
      (node (ref "U2") (pin "39") (pinfunction "39/OUT1A/MISO1/A15_39") (pintype "passive"))
    )
    (net (code "62") (name "unconnected-(U2-40{slash}A16-Pad40)") (class "Default")
      (node (ref "U2") (pin "40") (pinfunction "40/A16_40") (pintype "passive"))
    )
    (net (code "63") (name "unconnected-(U2-41{slash}A17-Pad41)") (class "Default")
      (node (ref "U2") (pin "41") (pinfunction "41/A17_41") (pintype "passive"))
    )
    (net (code "64") (name "unconnected-(U5-A4-Pad5)") (class "Default")
      (node (ref "U5") (pin "5") (pinfunction "A4_5") (pintype "passive"))
    )
    (net (code "65") (name "unconnected-(U5-B4-Pad10)") (class "Default")
      (node (ref "U5") (pin "10") (pinfunction "B4_10") (pintype "passive"))
    )
    (net (code "66") (name "unconnected-(U14-INT1-Pad8)") (class "Default")
      (node (ref "U14") (pin "8") (pinfunction "INT1_8") (pintype "passive"))
    )
    (net (code "67") (name "unconnected-(U14-INT2-Pad9)") (class "Default")
      (node (ref "U14") (pin "9") (pinfunction "INT2_9") (pintype "passive"))
    )
    (net (code "68") (name "unconnected-(U16-INT1-Pad8)") (class "Default")
      (node (ref "U16") (pin "8") (pinfunction "INT1_8") (pintype "passive"))
    )
    (net (code "69") (name "unconnected-(U16-INT2-Pad9)") (class "Default")
      (node (ref "U16") (pin "9") (pinfunction "INT2_9") (pintype "passive"))
    )
    (net (code "70") (name "unconnected-(U17-INT1-Pad8)") (class "Default")
      (node (ref "U17") (pin "8") (pinfunction "INT1_8") (pintype "passive"))
    )
    (net (code "71") (name "unconnected-(U17-INT2-Pad9)") (class "Default")
      (node (ref "U17") (pin "9") (pinfunction "INT2_9") (pintype "passive"))
    )
    (net (code "72") (name "unconnected-(U19-INT1-Pad8)") (class "Default")
      (node (ref "U19") (pin "8") (pinfunction "INT1_8") (pintype "passive"))
    )
    (net (code "73") (name "unconnected-(U19-INT2-Pad9)") (class "Default")
      (node (ref "U19") (pin "9") (pinfunction "INT2_9") (pintype "passive"))
    )
  )
)
